# schematic.net
KiCad netlist of a schematic drawn in EasyEDA
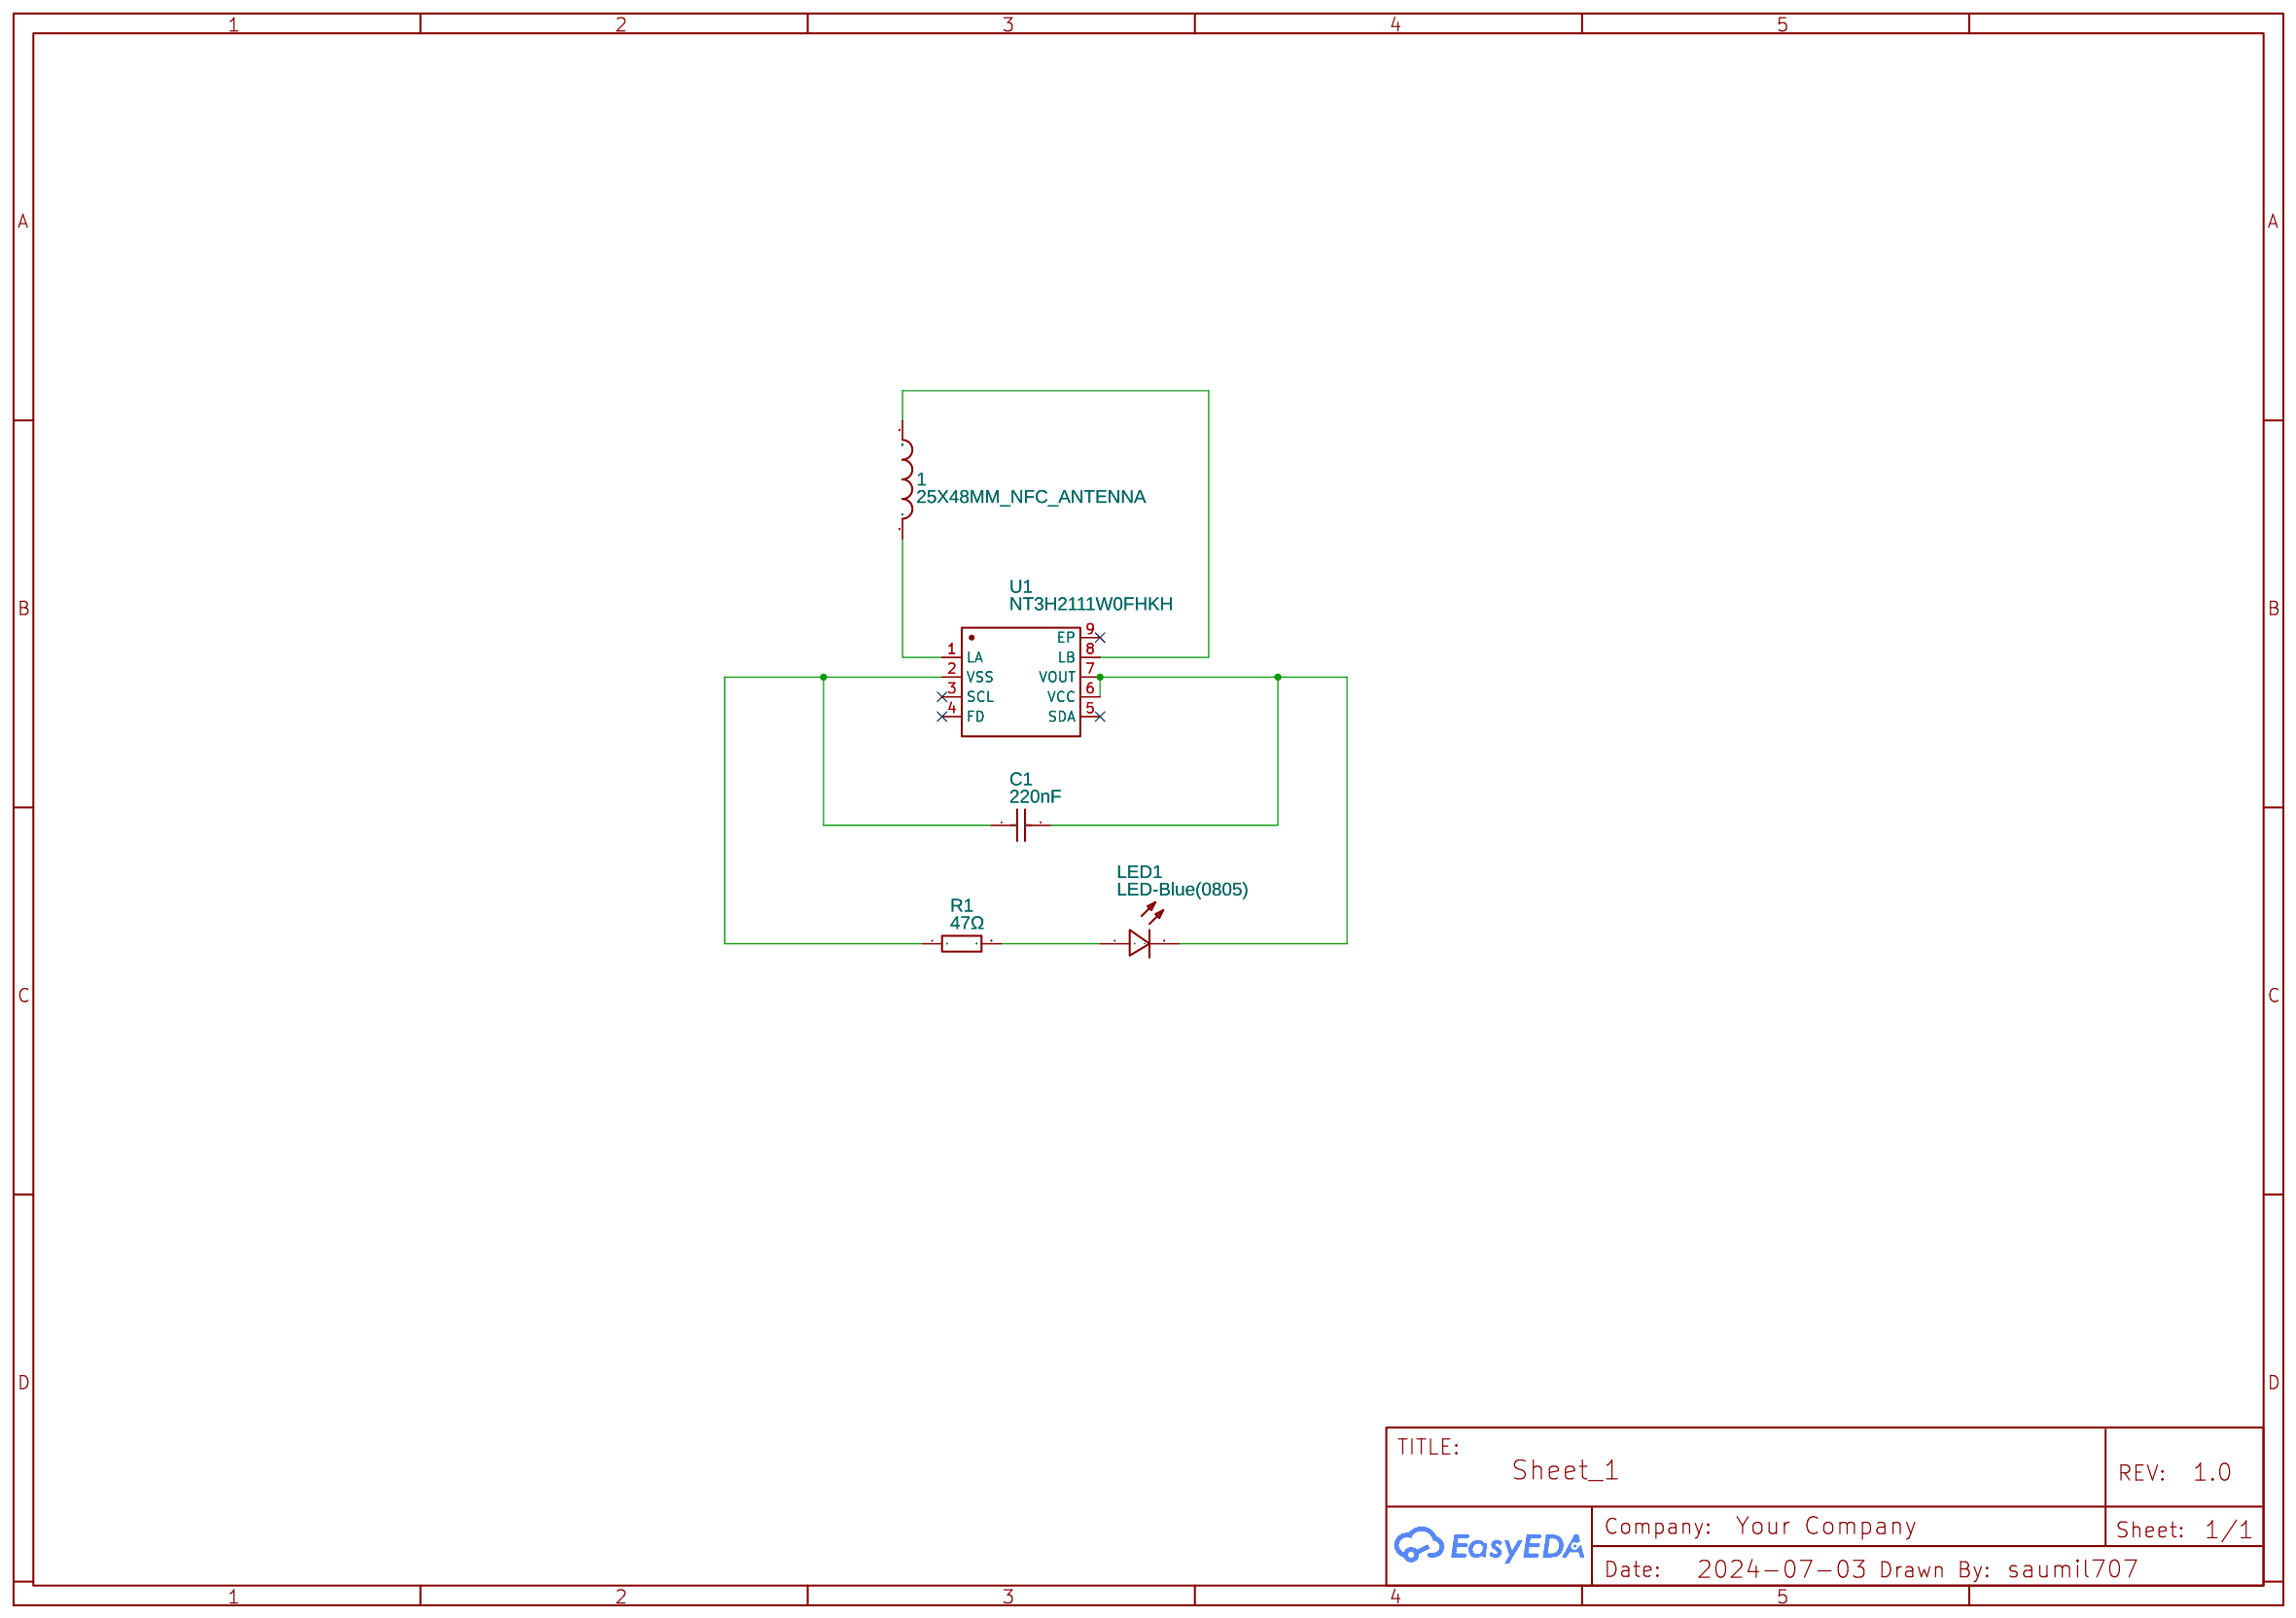
[diagram p0: schematic sheet]

(export (version "E")
  (design (tool "Eeschema 10.0.6"))
  (components
    (comp (ref "1") (value "25X48MM_NFC_ANTENNA") (libsource (lib "") (part "25X48MM_NFC_ANTENNA")))
    (comp (ref "C1")
      (value "220nF")
      (fields
        (field (name "Manufacturer Part") "CL10B224KA8NNNC")
        (field (name "Manufacturer") "SAMSUNG(三星)")
      )
      (libsource (lib "") (part "CL10B224KA8NNNC"))
    )
    (comp (ref "LED1")
      (value "LED-Blue(0805)")
      (fields
        (field (name "Manufacturer Part") "17-21/BHC-XL2M2TY/3T")
        (field (name "Manufacturer") "Everlight Elec")
      )
      (libsource (lib "") (part "LED-Blue(0805)"))
    )
    (comp (ref "R1")
      (value "47Ω")
      (fields
        (field (name "Manufacturer Part") "0603WAF470JT5E")
        (field (name "Manufacturer") "UNI-ROYAL(厚声)")
      )
      (libsource (lib "") (part "0603WAF470JT5E"))
    )
    (comp (ref "U1")
      (value "NT3H2111W0FHKH")
      (fields (field (name "Manufacturer") "NXP(恩智浦)"))
      (libsource (lib "") (part "NT3H2111W0FHKH"))
    )
  )
  (nets
    (net (code "1") (name "Net-(LED1-+)") (class "Default")
      (node (ref "LED1") (pin "1") (pinfunction "+_1") (pintype "unspecified"))
      (node (ref "R1") (pin "2") (pinfunction "2_2") (pintype "input"))
    )
    (net (code "2") (name "Net-(LED1--)") (class "Default")
      (node (ref "C1") (pin "2") (pinfunction "2_2") (pintype "input"))
      (node (ref "LED1") (pin "2") (pinfunction "-_2") (pintype "unspecified"))
      (node (ref "U1") (pin "6") (pinfunction "VCC_6") (pintype "unspecified"))
      (node (ref "U1") (pin "7") (pinfunction "VOUT_7") (pintype "unspecified"))
    )
    (net (code "3") (name "Net-(U1-LA)") (class "Default")
      (node (ref "1") (pin "P$2") (pinfunction "P$2_P$2") (pintype "bidirectional"))
      (node (ref "U1") (pin "1") (pinfunction "LA_1") (pintype "unspecified"))
    )
    (net (code "4") (name "Net-(U1-LB)") (class "Default")
      (node (ref "1") (pin "P$1") (pinfunction "P$1_P$1") (pintype "bidirectional"))
      (node (ref "U1") (pin "8") (pinfunction "LB_8") (pintype "unspecified"))
    )
    (net (code "5") (name "Net-(U1-VSS)") (class "Default")
      (node (ref "C1") (pin "1") (pinfunction "1_1") (pintype "input"))
      (node (ref "R1") (pin "1") (pinfunction "1_1") (pintype "input"))
      (node (ref "U1") (pin "2") (pinfunction "VSS_2") (pintype "unspecified"))
    )
    (net (code "6") (name "unconnected-(U1-EP-Pad9)") (class "Default")
      (node (ref "U1") (pin "9") (pinfunction "EP_9") (pintype "unspecified+no_connect"))
    )
    (net (code "7") (name "unconnected-(U1-FD-Pad4)") (class "Default")
      (node (ref "U1") (pin "4") (pinfunction "FD_4") (pintype "unspecified+no_connect"))
    )
    (net (code "8") (name "unconnected-(U1-SCL-Pad3)") (class "Default")
      (node (ref "U1") (pin "3") (pinfunction "SCL_3") (pintype "unspecified+no_connect"))
    )
    (net (code "9") (name "unconnected-(U1-SDA-Pad5)") (class "Default")
      (node (ref "U1") (pin "5") (pinfunction "SDA_5") (pintype "unspecified+no_connect"))
    )
  )
)
